# Serial.net
KiCad netlist of a schematic drawn in Altium Designer
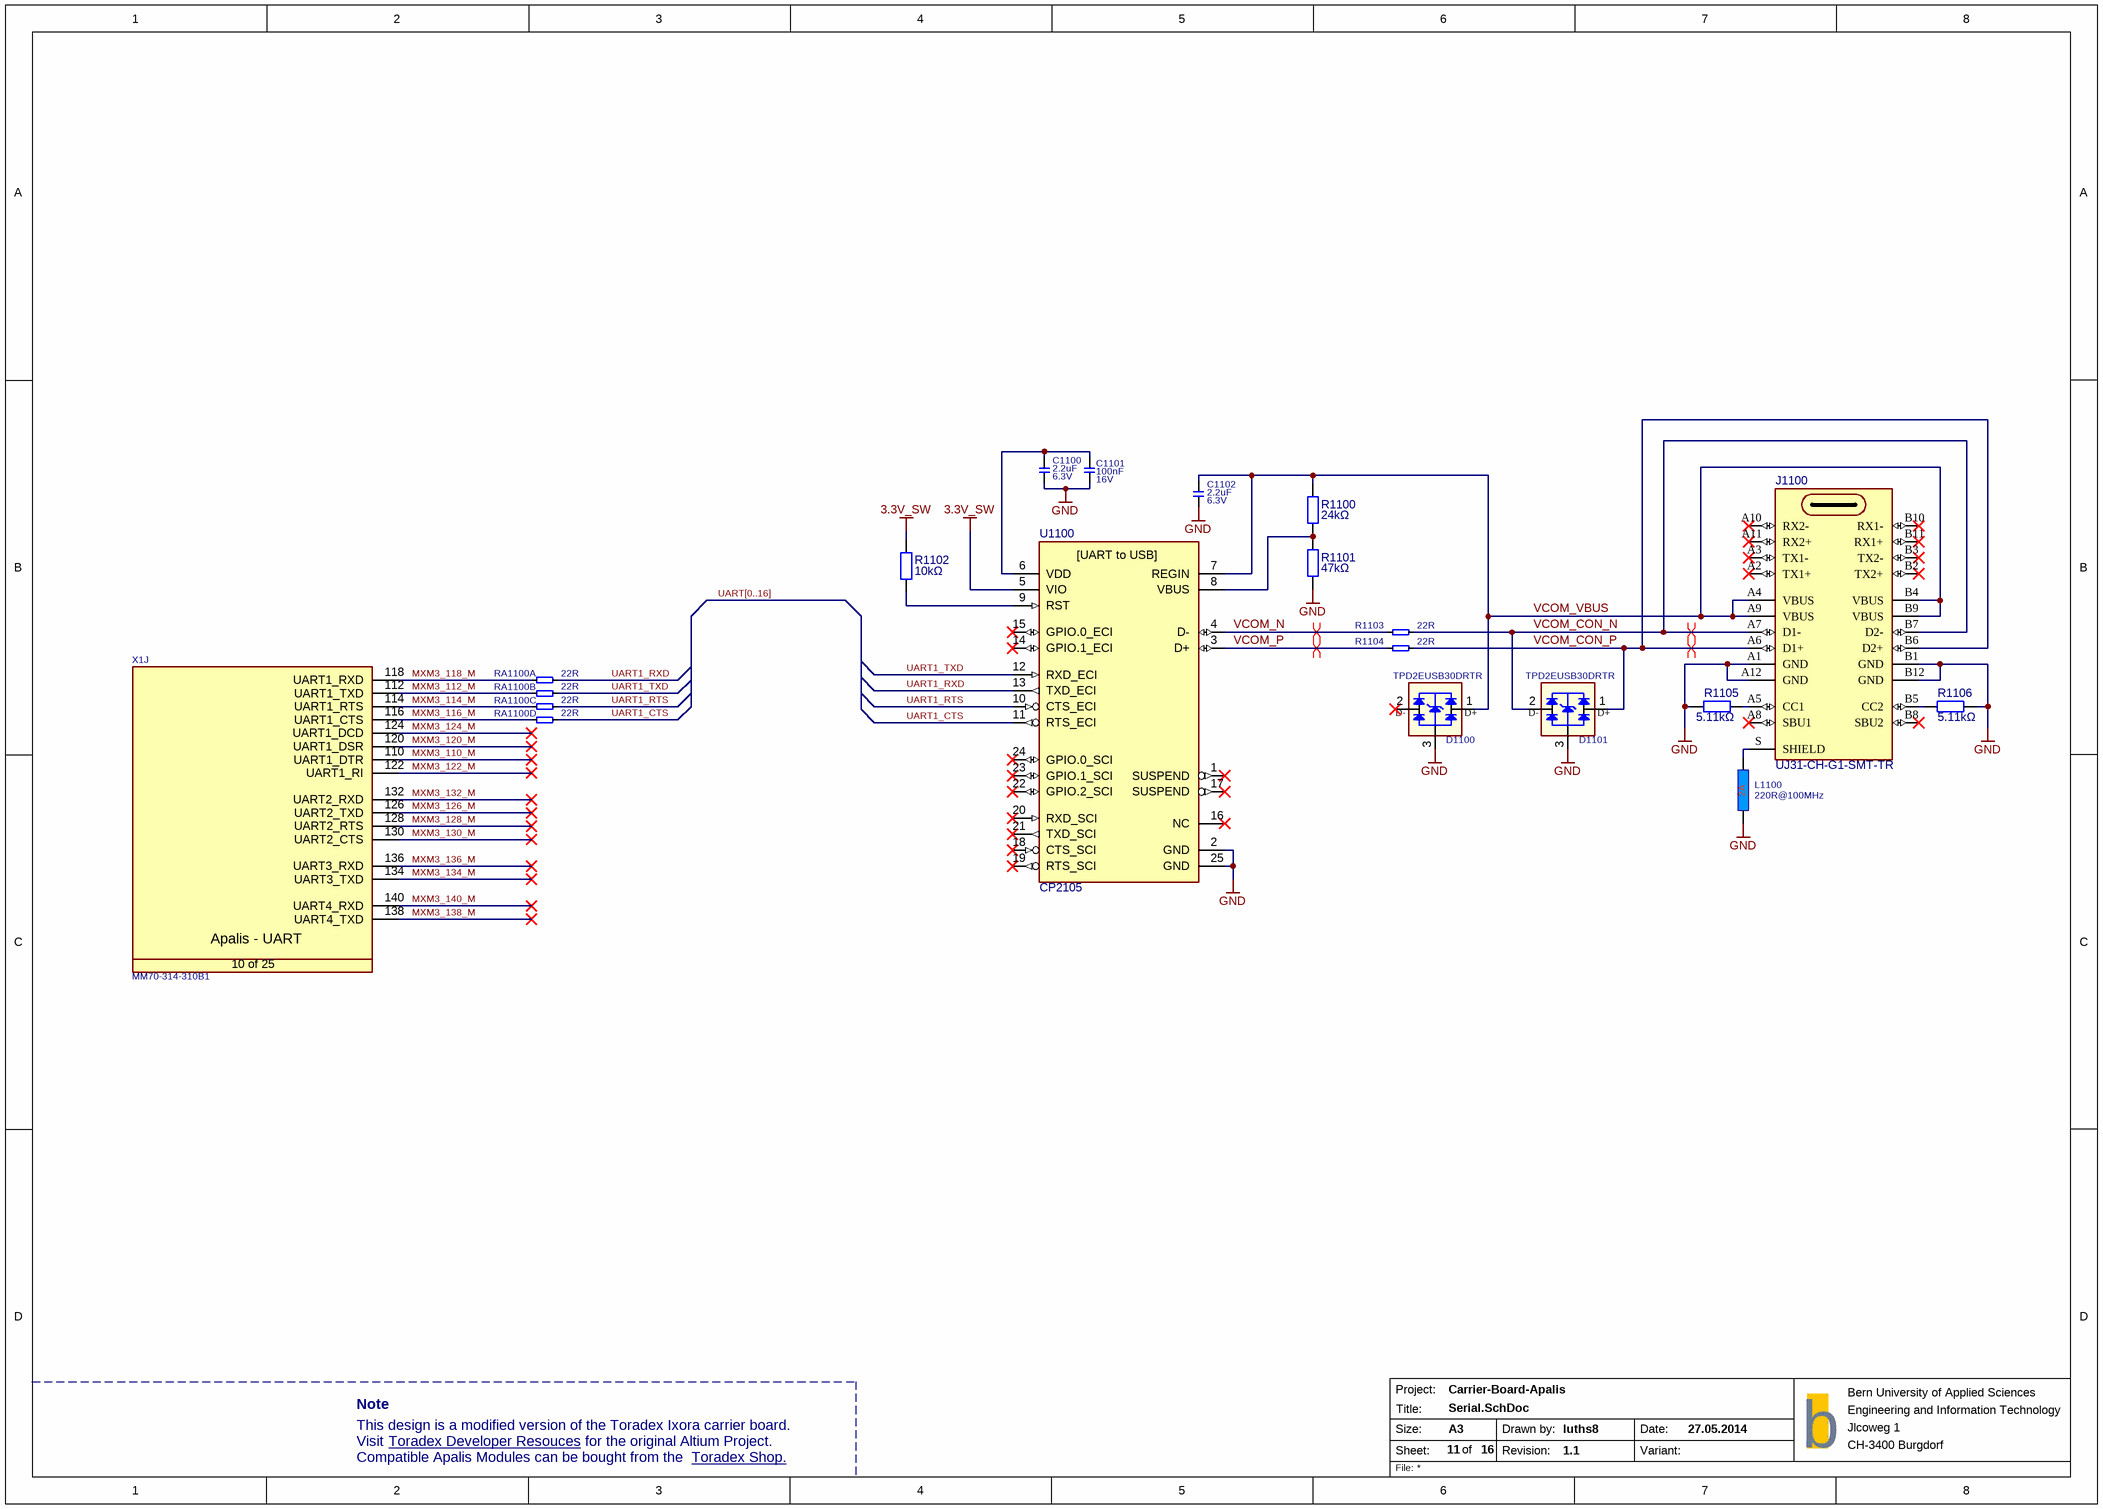
[diagram p0: Serial.SchDoc]

(export (version "E")
  (design (tool "Eeschema 10.0.6"))
  (components
    (comp (ref "C1100")
      (value "2.2uF")
      (footprint "SMD0603CAP")
      (description "Capacitor Ceramic X5R 2.2uF 6.3V 20% 0603")
      (fields (field (name "TOLERANCE") "20%") (field (name "RATING") "6.3V"))
      (libsource (lib "Ixora") (part "C-X5R-2.2uF-6.3V-20%-0603"))
    )
    (comp (ref "C1101")
      (value "100nF")
      (footprint "SMD0603CAP")
      (description "Capacitor Ceramic X7R 100nF 16V 10% 0603")
      (fields (field (name "TOLERANCE") "10%") (field (name "RATING") "16V"))
      (libsource (lib "Ixora") (part "C-X7R-100nF-16V-10%-0402"))
    )
    (comp (ref "C1102")
      (value "2.2uF")
      (footprint "SMD0603CAP")
      (description "Capacitor Ceramic X5R 2.2uF 6.3V 20% 0603")
      (fields (field (name "TOLERANCE") "20%") (field (name "RATING") "6.3V"))
      (libsource (lib "Ixora") (part "C-X5R-2.2uF-6.3V-20%-0603"))
    )
    (comp (ref "D1100")
      (value "TPD2EUSB30DRTR")
      (footprint "T_TI_TPD2EUSB30DRTR")
      (description "2 Channel Protection for Super Speed USB3.0")
      (fields (field (name "MANUFACTURER PART NO.") "TPD2EUSB30DRTR"))
      (libsource (lib "Ixora") (part "D-TI-TPD2EUSB30DRTR"))
    )
    (comp (ref "D1101")
      (value "TPD2EUSB30DRTR")
      (footprint "T_TI_TPD2EUSB30DRTR")
      (description "2 Channel Protection for Super Speed USB3.0")
      (fields (field (name "MANUFACTURER PART NO.") "TPD2EUSB30DRTR"))
      (libsource (lib "Ixora") (part "D-TI-TPD2EUSB30DRTR"))
    )
    (comp (ref "J1100")
      (value "UJ31-CH-G1-SMT-TR")
      (footprint "UJ31-CH-G1-SMT-TR")
      (description "USB Type C Jack")
      (libsource (lib "Audio-Streamer") (part "Connector USB C"))
    )
    (comp (ref "L1100")
      (value "220R@100MHz")
      (footprint "INDC1608X95N")
      (description "220R@100MHz 2A EMI FILTER")
      (fields (field (name "TOLERANCE") "25%"))
      (libsource (lib "Ixora") (part "L-220R@100MHz-2A-25%-0603"))
    )
    (comp (ref "R1100")
      (value "24kΩ")
      (footprint "SMD0603RES")
      (description "Resistor")
      (libsource (lib "Audio-Streamer") (part "Resistor"))
    )
    (comp (ref "R1101")
      (value "47kΩ")
      (footprint "SMD0603RES")
      (description "Resistor")
      (libsource (lib "Audio-Streamer") (part "Resistor"))
    )
    (comp (ref "R1102")
      (value "10kΩ")
      (footprint "SMD0603RES")
      (description "Resistor")
      (libsource (lib "Audio-Streamer") (part "Resistor"))
    )
    (comp (ref "R1103")
      (value "22R")
      (footprint "SMD0603RES")
      (description "Resistor 22 ohm 63mW 5% 0603")
      (fields (field (name "TOLERANCE") "5%"))
      (libsource (lib "Ixora") (part "R-22R-63mW-5%-0402"))
    )
    (comp (ref "R1104")
      (value "22R")
      (footprint "SMD0603RES")
      (description "Resistor 22 ohm 63mW 5% 0603")
      (fields (field (name "TOLERANCE") "5%"))
      (libsource (lib "Ixora") (part "R-22R-63mW-5%-0402"))
    )
    (comp (ref "R1105")
      (value "5.11kΩ")
      (footprint "SMD0603RES")
      (description "Resistor")
      (libsource (lib "Audio-Streamer") (part "Resistor"))
    )
    (comp (ref "R1106")
      (value "5.11kΩ")
      (footprint "SMD0603RES")
      (description "Resistor")
      (libsource (lib "") (part "Resistor_1"))
    )
    (comp (ref "RA1100")
      (value "22R")
      (footprint "T_Resistor_Array_X4")
      (description "Resistor Array 22 R 63mW 5% 1206")
      (fields (field (name "TOLERANCE") "5%"))
      (libsource (lib "Ixora") (part "RA-22R-63mW-5%-1206-div"))
    )
    (comp (ref "U1100")
      (value "CP2105")
      (footprint "QFN24")
      (description "USB to UART Bridge")
      (fields (field (name "MANUFACTURER PART NO.") "CP2105-F01-GMR"))
      (libsource (lib "Audio-Streamer") (part "CP2105"))
    )
    (comp (ref "X1")
      (value "CON-JAE-MM70-314-310B1-314-0.5mm")
      (footprint "T_JAE_MM70-314-310B1")
      (description "MXM3 Connector")
      (fields (field (name "MANUFACTURER PART NO.") "MM70-314-310B1"))
      (libsource (lib "Ixora") (part "CON-JAE-MM70-314-310B1-314-0.5mm"))
    )
  )
  (nets
    (net (code "18") (name "/MXM3_110_M") (class "Default")
      (node (ref "X1") (pin "110") (pinfunction "UART1_DTR_110") (pintype "passive+no_connect"))
    )
    (net (code "19") (name "/MXM3_112_M") (class "Default")
      (node (ref "RA1100") (pin "1") (pinfunction "1_1") (pintype "passive"))
      (node (ref "X1") (pin "112") (pinfunction "UART1_TXD_112") (pintype "passive"))
    )
    (net (code "20") (name "/MXM3_114_M") (class "Default")
      (node (ref "RA1100") (pin "2") (pinfunction "2_2") (pintype "passive"))
      (node (ref "X1") (pin "114") (pinfunction "UART1_RTS_114") (pintype "passive"))
    )
    (net (code "22") (name "/MXM3_118_M") (class "Default")
      (node (ref "RA1100") (pin "4") (pinfunction "4_4") (pintype "passive"))
      (node (ref "X1") (pin "118") (pinfunction "UART1_RXD_118") (pintype "passive"))
    )
    (net (code "23") (name "/MXM3_120_M") (class "Default")
      (node (ref "X1") (pin "120") (pinfunction "UART1_DSR_120") (pintype "passive+no_connect"))
    )
    (net (code "24") (name "/MXM3_122_M") (class "Default")
      (node (ref "X1") (pin "122") (pinfunction "UART1_RI_122") (pintype "passive+no_connect"))
    )
    (net (code "25") (name "/MXM3_124_M") (class "Default")
      (node (ref "X1") (pin "124") (pinfunction "UART1_DCD_124") (pintype "passive+no_connect"))
    )
    (net (code "26") (name "/MXM3_126_M") (class "Default")
      (node (ref "X1") (pin "126") (pinfunction "UART2_TXD_126") (pintype "passive+no_connect"))
    )
    (net (code "27") (name "/MXM3_128_M") (class "Default")
      (node (ref "X1") (pin "128") (pinfunction "UART2_RTS_128") (pintype "passive+no_connect"))
    )
    (net (code "28") (name "/MXM3_130_M") (class "Default")
      (node (ref "X1") (pin "130") (pinfunction "UART2_CTS_130") (pintype "passive+no_connect"))
    )
    (net (code "29") (name "/MXM3_132_M") (class "Default")
      (node (ref "X1") (pin "132") (pinfunction "UART2_RXD_132") (pintype "passive+no_connect"))
    )
    (net (code "30") (name "/MXM3_134_M") (class "Default")
      (node (ref "X1") (pin "134") (pinfunction "UART3_TXD_134") (pintype "passive+no_connect"))
    )
    (net (code "31") (name "/MXM3_136_M") (class "Default")
      (node (ref "X1") (pin "136") (pinfunction "UART3_RXD_136") (pintype "passive+no_connect"))
    )
    (net (code "32") (name "/MXM3_138_M") (class "Default")
      (node (ref "X1") (pin "138") (pinfunction "UART4_TXD_138") (pintype "passive+no_connect"))
    )
    (net (code "33") (name "/MXM3_140_M") (class "Default")
      (node (ref "X1") (pin "140") (pinfunction "UART4_RXD_140") (pintype "passive+no_connect"))
    )
    (net (code "34") (name "/UART1_CTS") (class "Default")
      (node (ref "RA1100") (pin "7") (pinfunction "7_7") (pintype "passive"))
      (node (ref "U1100") (pin "11") (pinfunction "RTS_ECI_11") (pintype "output"))
    )
    (net (code "35") (name "/UART1_RTS") (class "Default")
      (node (ref "RA1100") (pin "6") (pinfunction "6_6") (pintype "passive"))
      (node (ref "U1100") (pin "10") (pinfunction "CTS_ECI_10") (pintype "input"))
    )
    (net (code "36") (name "/UART1_RXD") (class "Default")
      (node (ref "RA1100") (pin "8") (pinfunction "8_8") (pintype "passive"))
      (node (ref "U1100") (pin "13") (pinfunction "TXD_ECI_13") (pintype "output"))
    )
    (net (code "37") (name "/UART1_TXD") (class "Default")
      (node (ref "RA1100") (pin "5") (pinfunction "5_5") (pintype "passive"))
      (node (ref "U1100") (pin "12") (pinfunction "RXD_ECI_12") (pintype "input"))
    )
    (net (code "39") (name "/VCOM_CON_N") (class "Default")
      (node (ref "D1101") (pin "2") (pinfunction "D-_2") (pintype "power_in"))
      (node (ref "J1100") (pin "A7") (pinfunction "D1-_A7") (pintype "bidirectional"))
      (node (ref "J1100") (pin "B7") (pinfunction "D2-_B7") (pintype "bidirectional"))
      (node (ref "R1103") (pin "2") (pinfunction "2_2") (pintype "passive"))
    )
    (net (code "40") (name "/VCOM_CON_P") (class "Default")
      (node (ref "D1101") (pin "1") (pinfunction "D+_1") (pintype "power_in"))
      (node (ref "J1100") (pin "A6") (pinfunction "D1+_A6") (pintype "bidirectional"))
      (node (ref "J1100") (pin "B6") (pinfunction "D2+_B6") (pintype "bidirectional"))
      (node (ref "R1104") (pin "2") (pinfunction "2_2") (pintype "passive"))
    )
    (net (code "41") (name "/VCOM_N") (class "Default")
      (node (ref "R1103") (pin "1") (pinfunction "1_1") (pintype "passive"))
      (node (ref "U1100") (pin "4") (pinfunction "D-_4") (pintype "bidirectional"))
    )
    (net (code "42") (name "/VCOM_P") (class "Default")
      (node (ref "R1104") (pin "1") (pinfunction "1_1") (pintype "passive"))
      (node (ref "U1100") (pin "3") (pinfunction "D+_3") (pintype "bidirectional"))
    )
    (net (code "43") (name "/VCOM_VBUS") (class "Default")
      (node (ref "C1102") (pin "2") (pinfunction "2_2") (pintype "passive"))
      (node (ref "D1100") (pin "1") (pinfunction "D+_1") (pintype "power_in"))
      (node (ref "J1100") (pin "A4") (pinfunction "VBUS_A4") (pintype "power_in"))
      (node (ref "J1100") (pin "A9") (pinfunction "VBUS_A9") (pintype "power_in"))
      (node (ref "J1100") (pin "B4") (pinfunction "VBUS_B4") (pintype "power_in"))
      (node (ref "J1100") (pin "B9") (pinfunction "VBUS_B9") (pintype "power_in"))
      (node (ref "R1100") (pin "2") (pinfunction "2_2") (pintype "passive"))
      (node (ref "U1100") (pin "7") (pinfunction "REGIN_7") (pintype "power_in"))
    )
    (net (code "44") (name "3.3V_SW") (class "Default")
      (node (ref "R1102") (pin "2") (pinfunction "2_2") (pintype "passive"))
      (node (ref "U1100") (pin "5") (pinfunction "VIO_5") (pintype "power_in"))
    )
    (net (code "45") (name "GND") (class "Default")
      (node (ref "C1100") (pin "1") (pinfunction "1_1") (pintype "passive"))
      (node (ref "C1101") (pin "1") (pinfunction "1_1") (pintype "passive"))
      (node (ref "C1102") (pin "1") (pinfunction "1_1") (pintype "passive"))
      (node (ref "D1100") (pin "3") (pinfunction "3_3") (pintype "power_in"))
      (node (ref "D1101") (pin "3") (pinfunction "3_3") (pintype "power_in"))
      (node (ref "J1100") (pin "A1") (pinfunction "GND_A1") (pintype "power_in"))
      (node (ref "J1100") (pin "A12") (pinfunction "GND_A12") (pintype "power_in"))
      (node (ref "J1100") (pin "B1") (pinfunction "GND_B1") (pintype "power_in"))
      (node (ref "J1100") (pin "B12") (pinfunction "GND_B12") (pintype "power_in"))
      (node (ref "L1100") (pin "1") (pinfunction "1_1") (pintype "passive"))
      (node (ref "R1101") (pin "1") (pinfunction "1_1") (pintype "passive"))
      (node (ref "R1105") (pin "1") (pinfunction "1_1") (pintype "passive"))
      (node (ref "R1106") (pin "1") (pinfunction "1_1") (pintype "passive"))
      (node (ref "U1100") (pin "2") (pinfunction "GND_2") (pintype "power_in"))
      (node (ref "U1100") (pin "25") (pinfunction "GND_25") (pintype "power_in"))
    )
    (net (code "46") (name "Net-(J1100-CC1)") (class "Default")
      (node (ref "J1100") (pin "A5") (pinfunction "CC1_A5") (pintype "bidirectional"))
      (node (ref "R1105") (pin "2") (pinfunction "2_2") (pintype "passive"))
    )
    (net (code "47") (name "Net-(J1100-CC2)") (class "Default")
      (node (ref "J1100") (pin "B5") (pinfunction "CC2_B5") (pintype "bidirectional"))
      (node (ref "R1106") (pin "2") (pinfunction "2_2") (pintype "passive"))
    )
    (net (code "48") (name "Net-(J1100-SHIELD)") (class "Default")
      (node (ref "J1100") (pin "S") (pinfunction "SHIELD_S") (pintype "power_in"))
      (node (ref "L1100") (pin "2") (pinfunction "2_2") (pintype "passive"))
    )
    (net (code "49") (name "Net-(U1100-RST)") (class "Default")
      (node (ref "R1102") (pin "1") (pinfunction "1_1") (pintype "passive"))
      (node (ref "U1100") (pin "9") (pinfunction "RST_9") (pintype "input"))
    )
    (net (code "50") (name "Net-(U1100-VBUS)") (class "Default")
      (node (ref "R1100") (pin "1") (pinfunction "1_1") (pintype "passive"))
      (node (ref "R1101") (pin "2") (pinfunction "2_2") (pintype "passive"))
      (node (ref "U1100") (pin "8") (pinfunction "VBUS_8") (pintype "power_in"))
    )
    (net (code "51") (name "Net-(U1100-VDD)") (class "Default")
      (node (ref "C1100") (pin "2") (pinfunction "2_2") (pintype "passive"))
      (node (ref "C1101") (pin "2") (pinfunction "2_2") (pintype "passive"))
      (node (ref "U1100") (pin "6") (pinfunction "VDD_6") (pintype "power_in"))
    )
    (net (code "52") (name "Net-(X1J-UART1_CTS)") (class "Default")
      (node (ref "RA1100") (pin "3") (pinfunction "3_3") (pintype "passive"))
      (node (ref "X1") (pin "116") (pinfunction "UART1_CTS_116") (pintype "passive"))
    )
    (net (code "53") (name "unconnected-(D1100-D--Pad2)") (class "Default")
      (node (ref "D1100") (pin "2") (pinfunction "D-_2") (pintype "power_in+no_connect"))
    )
    (net (code "54") (name "unconnected-(J1100-RX1+-PadB11)") (class "Default")
      (node (ref "J1100") (pin "B11") (pinfunction "RX1+_B11") (pintype "bidirectional+no_connect"))
    )
    (net (code "55") (name "unconnected-(J1100-RX1--PadB10)") (class "Default")
      (node (ref "J1100") (pin "B10") (pinfunction "RX1-_B10") (pintype "bidirectional+no_connect"))
    )
    (net (code "56") (name "unconnected-(J1100-RX2+-PadA11)") (class "Default")
      (node (ref "J1100") (pin "A11") (pinfunction "RX2+_A11") (pintype "bidirectional+no_connect"))
    )
    (net (code "57") (name "unconnected-(J1100-RX2--PadA10)") (class "Default")
      (node (ref "J1100") (pin "A10") (pinfunction "RX2-_A10") (pintype "bidirectional+no_connect"))
    )
    (net (code "58") (name "unconnected-(J1100-SBU1-PadA8)") (class "Default")
      (node (ref "J1100") (pin "A8") (pinfunction "SBU1_A8") (pintype "bidirectional+no_connect"))
    )
    (net (code "59") (name "unconnected-(J1100-SBU2-PadB8)") (class "Default")
      (node (ref "J1100") (pin "B8") (pinfunction "SBU2_B8") (pintype "bidirectional+no_connect"))
    )
    (net (code "60") (name "unconnected-(J1100-TX1+-PadA2)") (class "Default")
      (node (ref "J1100") (pin "A2") (pinfunction "TX1+_A2") (pintype "bidirectional+no_connect"))
    )
    (net (code "61") (name "unconnected-(J1100-TX1--PadA3)") (class "Default")
      (node (ref "J1100") (pin "A3") (pinfunction "TX1-_A3") (pintype "bidirectional+no_connect"))
    )
    (net (code "62") (name "unconnected-(J1100-TX2+-PadB2)") (class "Default")
      (node (ref "J1100") (pin "B2") (pinfunction "TX2+_B2") (pintype "bidirectional+no_connect"))
    )
    (net (code "63") (name "unconnected-(J1100-TX2--PadB3)") (class "Default")
      (node (ref "J1100") (pin "B3") (pinfunction "TX2-_B3") (pintype "bidirectional+no_connect"))
    )
    (net (code "64") (name "unconnected-(U1100-CTS_SCI-Pad18)") (class "Default")
      (node (ref "U1100") (pin "18") (pinfunction "CTS_SCI_18") (pintype "input+no_connect"))
    )
    (net (code "65") (name "unconnected-(U1100-GPIO.0_ECI-Pad15)") (class "Default")
      (node (ref "U1100") (pin "15") (pinfunction "GPIO.0_ECI_15") (pintype "bidirectional+no_connect"))
    )
    (net (code "66") (name "unconnected-(U1100-GPIO.0_SCI-Pad24)") (class "Default")
      (node (ref "U1100") (pin "24") (pinfunction "GPIO.0_SCI_24") (pintype "bidirectional+no_connect"))
    )
    (net (code "67") (name "unconnected-(U1100-GPIO.1_ECI-Pad14)") (class "Default")
      (node (ref "U1100") (pin "14") (pinfunction "GPIO.1_ECI_14") (pintype "bidirectional+no_connect"))
    )
    (net (code "68") (name "unconnected-(U1100-GPIO.1_SCI-Pad23)") (class "Default")
      (node (ref "U1100") (pin "23") (pinfunction "GPIO.1_SCI_23") (pintype "bidirectional+no_connect"))
    )
    (net (code "69") (name "unconnected-(U1100-GPIO.2_SCI-Pad22)") (class "Default")
      (node (ref "U1100") (pin "22") (pinfunction "GPIO.2_SCI_22") (pintype "bidirectional+no_connect"))
    )
    (net (code "70") (name "unconnected-(U1100-NC-Pad16)") (class "Default")
      (node (ref "U1100") (pin "16") (pinfunction "NC_16") (pintype "passive+no_connect"))
    )
    (net (code "71") (name "unconnected-(U1100-RTS_SCI-Pad19)") (class "Default")
      (node (ref "U1100") (pin "19") (pinfunction "RTS_SCI_19") (pintype "output+no_connect"))
    )
    (net (code "72") (name "unconnected-(U1100-RXD_SCI-Pad20)") (class "Default")
      (node (ref "U1100") (pin "20") (pinfunction "RXD_SCI_20") (pintype "input+no_connect"))
    )
    (net (code "73") (name "unconnected-(U1100-SUSPEND-Pad1)") (class "Default")
      (node (ref "U1100") (pin "1") (pinfunction "SUSPEND_1") (pintype "output+no_connect"))
    )
    (net (code "74") (name "unconnected-(U1100-SUSPEND-Pad17)") (class "Default")
      (node (ref "U1100") (pin "17") (pinfunction "SUSPEND_17") (pintype "output+no_connect"))
    )
    (net (code "75") (name "unconnected-(U1100-TXD_SCI-Pad21)") (class "Default")
      (node (ref "U1100") (pin "21") (pinfunction "TXD_SCI_21") (pintype "output+no_connect"))
    )
  )
)
